# pwr_fpga.net
KiCad netlist of a schematic drawn in Altium Designer
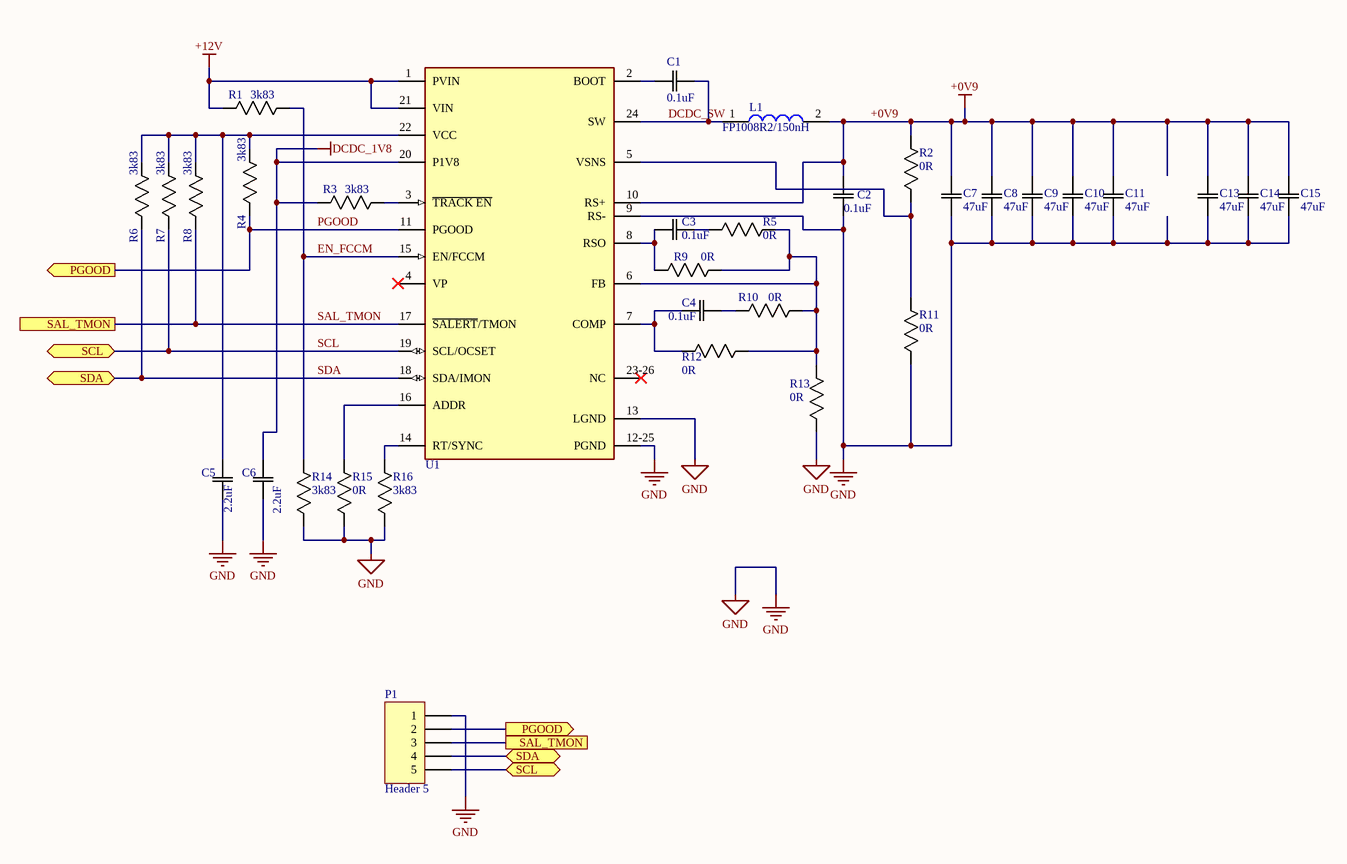
[diagram p0: pwr_fpga.SchDoc]

(export (version "E")
  (design (tool "Eeschema 10.0.6"))
  (components
    (comp (ref "C1")
      (value "0.1uF")
      (footprint "cap_UMK105 CG080CV-F_TAY")
      (description "No Description Available")
      (fields
        (field (name "MANUFACTURER_PART_NUMBER") "TMK105B7103KV-F")
        (field (name "COPYRIGHT") "Copyright (C) 2018 Accelerated Designs. All rights reserved")
      )
      (libsource (lib "2020-09-28_11-29-19") (part "TMK105B7103KV-F"))
    )
    (comp (ref "C2")
      (value "0.1uF")
      (footprint "cap_UMK105 CG080CV-F_TAY")
      (description "No Description Available")
      (fields
        (field (name "MANUFACTURER_PART_NUMBER") "TMK105B7103KV-F")
        (field (name "COPYRIGHT") "Copyright (C) 2018 Accelerated Designs. All rights reserved")
      )
      (libsource (lib "2020-09-28_11-29-19") (part "TMK105B7103KV-F"))
    )
    (comp (ref "C3")
      (value "0.1uF")
      (footprint "cap_UMK105 CG080CV-F_TAY")
      (description "No Description Available")
      (fields
        (field (name "MANUFACTURER_PART_NUMBER") "TMK105B7103KV-F")
        (field (name "COPYRIGHT") "Copyright (C) 2018 Accelerated Designs. All rights reserved")
      )
      (libsource (lib "2020-09-28_11-29-19") (part "TMK105B7103KV-F"))
    )
    (comp (ref "C4")
      (value "0.1uF")
      (footprint "cap_UMK105 CG080CV-F_TAY")
      (description "No Description Available")
      (fields
        (field (name "MANUFACTURER_PART_NUMBER") "TMK105B7103KV-F")
        (field (name "COPYRIGHT") "Copyright (C) 2018 Accelerated Designs. All rights reserved")
      )
      (libsource (lib "2020-09-28_11-29-19") (part "TMK105B7103KV-F"))
    )
    (comp (ref "C5")
      (value "2.2uF")
      (footprint "cap_UMK105 CG080CV-F_TAY")
      (description "No Description Available")
      (fields
        (field (name "MANUFACTURER_PART_NUMBER") "TMK105B7103KV-F")
        (field (name "COPYRIGHT") "Copyright (C) 2018 Accelerated Designs. All rights reserved")
      )
      (libsource (lib "2020-09-28_11-29-19") (part "TMK105B7103KV-F"))
    )
    (comp (ref "C6")
      (value "2.2uF")
      (footprint "cap_UMK105 CG080CV-F_TAY")
      (description "No Description Available")
      (fields
        (field (name "MANUFACTURER_PART_NUMBER") "TMK105B7103KV-F")
        (field (name "COPYRIGHT") "Copyright (C) 2018 Accelerated Designs. All rights reserved")
      )
      (libsource (lib "2020-09-28_11-29-19") (part "TMK105B7103KV-F"))
    )
    (comp (ref "C7")
      (value "47uF")
      (footprint "CAPC220145_140N_KEM")
      (description "No Description Available")
      (fields
        (field (name "MANUFACTURER_PART_NUMBER") "C0805C475K4PAC")
        (field (name "COPYRIGHT") "Copyright (C) 2018 Accelerated Designs. All rights reserved")
      )
      (libsource (lib "2020-10-01_03-11-46") (part "C0805C475K4PAC"))
    )
    (comp (ref "C8")
      (value "47uF")
      (footprint "CAPC220145_140N_KEM")
      (description "No Description Available")
      (fields
        (field (name "MANUFACTURER_PART_NUMBER") "C0805C475K4PAC")
        (field (name "COPYRIGHT") "Copyright (C) 2018 Accelerated Designs. All rights reserved")
      )
      (libsource (lib "2020-10-01_03-11-46") (part "C0805C475K4PAC"))
    )
    (comp (ref "C9")
      (value "47uF")
      (footprint "CAPC220145_140N_KEM")
      (description "No Description Available")
      (fields
        (field (name "MANUFACTURER_PART_NUMBER") "C0805C475K4PAC")
        (field (name "COPYRIGHT") "Copyright (C) 2018 Accelerated Designs. All rights reserved")
      )
      (libsource (lib "2020-10-01_03-11-46") (part "C0805C475K4PAC"))
    )
    (comp (ref "C10")
      (value "47uF")
      (footprint "CAPC220145_140N_KEM")
      (description "No Description Available")
      (fields
        (field (name "MANUFACTURER_PART_NUMBER") "C0805C475K4PAC")
        (field (name "COPYRIGHT") "Copyright (C) 2018 Accelerated Designs. All rights reserved")
      )
      (libsource (lib "2020-10-01_03-11-46") (part "C0805C475K4PAC"))
    )
    (comp (ref "C11")
      (value "47uF")
      (footprint "CAPC220145_140N_KEM")
      (description "No Description Available")
      (fields
        (field (name "MANUFACTURER_PART_NUMBER") "C0805C475K4PAC")
        (field (name "COPYRIGHT") "Copyright (C) 2018 Accelerated Designs. All rights reserved")
      )
      (libsource (lib "2020-10-01_03-11-46") (part "C0805C475K4PAC"))
    )
    (comp (ref "C13")
      (value "47uF")
      (footprint "CAPC220145_140N_KEM")
      (description "No Description Available")
      (fields
        (field (name "MANUFACTURER_PART_NUMBER") "C0805C475K4PAC")
        (field (name "COPYRIGHT") "Copyright (C) 2018 Accelerated Designs. All rights reserved")
      )
      (libsource (lib "2020-10-01_03-11-46") (part "C0805C475K4PAC"))
    )
    (comp (ref "C14")
      (value "47uF")
      (footprint "CAPC220145_140N_KEM")
      (description "No Description Available")
      (fields
        (field (name "MANUFACTURER_PART_NUMBER") "C0805C475K4PAC")
        (field (name "COPYRIGHT") "Copyright (C) 2018 Accelerated Designs. All rights reserved")
      )
      (libsource (lib "2020-10-01_03-11-46") (part "C0805C475K4PAC"))
    )
    (comp (ref "C15")
      (value "47uF")
      (footprint "CAPC220145_140N_KEM")
      (description "No Description Available")
      (fields
        (field (name "MANUFACTURER_PART_NUMBER") "C0805C475K4PAC")
        (field (name "COPYRIGHT") "Copyright (C) 2018 Accelerated Designs. All rights reserved")
      )
      (libsource (lib "2020-10-01_03-11-46") (part "C0805C475K4PAC"))
    )
    (comp (ref "L1")
      (value "FP1008R2/150nH")
      (footprint "SamacSys:INDM10880X800N")
      (description "Inductor")
      (fields
        (field (name "MANUFACTURER_PART_NUMBER") "FP1008R2-R120-R")
        (field (name "MOUSER PART NUMBER") "704-FP1008R2-R120-R")
      )
      (libsource (lib "*") (part "FP1008R2-R120-R"))
    )
    (comp (ref "P1")
      (value "Header 5")
      (footprint "HDR1X5")
      (description "Header, 5-Pin")
      (fields (field (name "PUBLISHER") "Altium Limited"))
      (libsource (lib "Miscellaneous Connectors") (part "Header 5"))
    )
    (comp (ref "R1")
      (value "3k83")
      (footprint "0402_PAN")
      (description "No Description Available")
      (fields
        (field (name "MANUFACTURER_PART_NUMBER") "ERJ2RHD2400X")
        (field (name "COPYRIGHT") "Copyright (C) 2018 Accelerated Designs. All rights reserved")
      )
      (libsource (lib "2020-09-26_12-38-29") (part "ERJ2RHD2400X"))
    )
    (comp (ref "R2")
      (value "0R")
      (footprint "0402_PAN")
      (description "No Description Available")
      (fields
        (field (name "MANUFACTURER_PART_NUMBER") "ERJ2RHD2400X")
        (field (name "COPYRIGHT") "Copyright (C) 2018 Accelerated Designs. All rights reserved")
      )
      (libsource (lib "2020-09-26_12-38-29") (part "ERJ2RHD2400X"))
    )
    (comp (ref "R3")
      (value "3k83")
      (footprint "0402_PAN")
      (description "No Description Available")
      (fields
        (field (name "MANUFACTURER_PART_NUMBER") "ERJ2RHD2400X")
        (field (name "COPYRIGHT") "Copyright (C) 2018 Accelerated Designs. All rights reserved")
      )
      (libsource (lib "2020-09-26_12-38-29") (part "ERJ2RHD2400X"))
    )
    (comp (ref "R4")
      (value "3k83")
      (footprint "0402_PAN")
      (description "No Description Available")
      (fields
        (field (name "MANUFACTURER_PART_NUMBER") "ERJ2RHD2400X")
        (field (name "COPYRIGHT") "Copyright (C) 2018 Accelerated Designs. All rights reserved")
      )
      (libsource (lib "2020-09-26_12-38-29") (part "ERJ2RHD2400X"))
    )
    (comp (ref "R5")
      (value "0R")
      (footprint "0402_PAN")
      (description "No Description Available")
      (fields
        (field (name "MANUFACTURER_PART_NUMBER") "ERJ2RHD2400X")
        (field (name "COPYRIGHT") "Copyright (C) 2018 Accelerated Designs. All rights reserved")
      )
      (libsource (lib "2020-09-26_12-38-29") (part "ERJ2RHD2400X"))
    )
    (comp (ref "R6")
      (value "3k83")
      (footprint "0402_PAN")
      (description "No Description Available")
      (fields
        (field (name "MANUFACTURER_PART_NUMBER") "ERJ2RHD2400X")
        (field (name "COPYRIGHT") "Copyright (C) 2018 Accelerated Designs. All rights reserved")
      )
      (libsource (lib "2020-09-26_12-38-29") (part "ERJ2RHD2400X"))
    )
    (comp (ref "R7")
      (value "3k83")
      (footprint "0402_PAN")
      (description "No Description Available")
      (fields
        (field (name "MANUFACTURER_PART_NUMBER") "ERJ2RHD2400X")
        (field (name "COPYRIGHT") "Copyright (C) 2018 Accelerated Designs. All rights reserved")
      )
      (libsource (lib "2020-09-26_12-38-29") (part "ERJ2RHD2400X"))
    )
    (comp (ref "R8")
      (value "3k83")
      (footprint "0402_PAN")
      (description "No Description Available")
      (fields
        (field (name "MANUFACTURER_PART_NUMBER") "ERJ2RHD2400X")
        (field (name "COPYRIGHT") "Copyright (C) 2018 Accelerated Designs. All rights reserved")
      )
      (libsource (lib "2020-09-26_12-38-29") (part "ERJ2RHD2400X"))
    )
    (comp (ref "R9")
      (value "0R")
      (footprint "0402_PAN")
      (description "No Description Available")
      (fields
        (field (name "MANUFACTURER_PART_NUMBER") "ERJ2RHD2400X")
        (field (name "COPYRIGHT") "Copyright (C) 2018 Accelerated Designs. All rights reserved")
      )
      (libsource (lib "2020-09-26_12-38-29") (part "ERJ2RHD2400X"))
    )
    (comp (ref "R10")
      (value "0R")
      (footprint "0402_PAN")
      (description "No Description Available")
      (fields
        (field (name "MANUFACTURER_PART_NUMBER") "ERJ2RHD2400X")
        (field (name "COPYRIGHT") "Copyright (C) 2018 Accelerated Designs. All rights reserved")
      )
      (libsource (lib "2020-09-26_12-38-29") (part "ERJ2RHD2400X"))
    )
    (comp (ref "R11")
      (value "0R")
      (footprint "0402_PAN")
      (description "No Description Available")
      (fields
        (field (name "MANUFACTURER_PART_NUMBER") "ERJ2RHD2400X")
        (field (name "COPYRIGHT") "Copyright (C) 2018 Accelerated Designs. All rights reserved")
      )
      (libsource (lib "2020-09-26_12-38-29") (part "ERJ2RHD2400X"))
    )
    (comp (ref "R12")
      (value "0R")
      (footprint "0402_PAN")
      (description "No Description Available")
      (fields
        (field (name "MANUFACTURER_PART_NUMBER") "ERJ2RHD2400X")
        (field (name "COPYRIGHT") "Copyright (C) 2018 Accelerated Designs. All rights reserved")
      )
      (libsource (lib "2020-09-26_12-38-29") (part "ERJ2RHD2400X"))
    )
    (comp (ref "R13")
      (value "0R")
      (footprint "0402_PAN")
      (description "No Description Available")
      (fields
        (field (name "MANUFACTURER_PART_NUMBER") "ERJ2RHD2400X")
        (field (name "COPYRIGHT") "Copyright (C) 2018 Accelerated Designs. All rights reserved")
      )
      (libsource (lib "2020-09-26_12-38-29") (part "ERJ2RHD2400X"))
    )
    (comp (ref "R14")
      (value "3k83")
      (footprint "0402_PAN")
      (description "No Description Available")
      (fields
        (field (name "MANUFACTURER_PART_NUMBER") "ERJ2RHD2400X")
        (field (name "COPYRIGHT") "Copyright (C) 2018 Accelerated Designs. All rights reserved")
      )
      (libsource (lib "2020-09-26_12-38-29") (part "ERJ2RHD2400X"))
    )
    (comp (ref "R15")
      (value "0R")
      (footprint "0402_PAN")
      (description "No Description Available")
      (fields
        (field (name "MANUFACTURER_PART_NUMBER") "ERJ2RHD2400X")
        (field (name "COPYRIGHT") "Copyright (C) 2018 Accelerated Designs. All rights reserved")
      )
      (libsource (lib "2020-09-26_12-38-29") (part "ERJ2RHD2400X"))
    )
    (comp (ref "R16")
      (value "3k83")
      (footprint "0402_PAN")
      (description "No Description Available")
      (fields
        (field (name "MANUFACTURER_PART_NUMBER") "ERJ2RHD2400X")
        (field (name "COPYRIGHT") "Copyright (C) 2018 Accelerated Designs. All rights reserved")
      )
      (libsource (lib "2020-09-26_12-38-29") (part "ERJ2RHD2400X"))
    )
    (comp (ref "U1")
      (value "IR38064MTRPBF")
      (footprint "Infineon_Technologies_PG-IQFN-34_MFG")
      (libsource (lib "IR38064MTRPBF") (part "IR38064MTRPBF"))
    )
  )
  (nets
    (net (code "1") (name "+0V9") (class "Default")
      (node (ref "C10") (pin "2") (pinfunction "2_2") (pintype "passive"))
      (node (ref "C11") (pin "2") (pinfunction "2_2") (pintype "passive"))
      (node (ref "C13") (pin "2") (pinfunction "2_2") (pintype "passive"))
      (node (ref "C14") (pin "2") (pinfunction "2_2") (pintype "passive"))
      (node (ref "C15") (pin "2") (pinfunction "2_2") (pintype "passive"))
      (node (ref "C2") (pin "2") (pinfunction "2_2") (pintype "passive"))
      (node (ref "C7") (pin "2") (pinfunction "2_2") (pintype "passive"))
      (node (ref "C8") (pin "2") (pinfunction "2_2") (pintype "passive"))
      (node (ref "C9") (pin "2") (pinfunction "2_2") (pintype "passive"))
      (node (ref "L1") (pin "2") (pinfunction "2_2") (pintype "passive"))
      (node (ref "R2") (pin "1") (pinfunction "1_1") (pintype "passive"))
      (node (ref "U1") (pin "10") (pinfunction "RS+_10") (pintype "tri_state"))
    )
    (net (code "2") (name "+12V") (class "Default")
      (node (ref "R1") (pin "2") (pinfunction "2_2") (pintype "passive"))
      (node (ref "U1") (pin "1") (pinfunction "PVIN_1") (pintype "power_in"))
      (node (ref "U1") (pin "21") (pinfunction "VIN_21") (pintype "power_in"))
    )
    (net (code "3") (name "/DCDC_SW") (class "Default")
      (node (ref "C1") (pin "2") (pinfunction "2_2") (pintype "passive"))
      (node (ref "L1") (pin "1") (pinfunction "1_1") (pintype "passive"))
      (node (ref "U1") (pin "24") (pinfunction "SW_24") (pintype "passive"))
    )
    (net (code "4") (name "/EN_FCCM") (class "Default")
      (node (ref "R1") (pin "1") (pinfunction "1_1") (pintype "passive"))
      (node (ref "R14") (pin "1") (pinfunction "1_1") (pintype "passive"))
      (node (ref "U1") (pin "15") (pinfunction "EN/FCCM_15") (pintype "input"))
    )
    (net (code "5") (name "/PGOOD") (class "Default")
      (node (ref "P1") (pin "2") (pinfunction "2_2") (pintype "passive"))
      (node (ref "R4") (pin "1") (pinfunction "1_1") (pintype "passive"))
      (node (ref "U1") (pin "11") (pinfunction "PGOOD_11") (pintype "open_collector"))
    )
    (net (code "6") (name "/SAL_TMON") (class "Default")
      (node (ref "P1") (pin "3") (pinfunction "3_3") (pintype "passive"))
      (node (ref "R8") (pin "1") (pinfunction "1_1") (pintype "passive"))
      (node (ref "U1") (pin "17") (pinfunction "~{SALERT}/TMON_17") (pintype "open_collector"))
    )
    (net (code "7") (name "/SCL") (class "Default")
      (node (ref "P1") (pin "5") (pinfunction "5_5") (pintype "passive"))
      (node (ref "R7") (pin "1") (pinfunction "1_1") (pintype "passive"))
      (node (ref "U1") (pin "19") (pinfunction "SCL/OCSET_19") (pintype "bidirectional"))
    )
    (net (code "8") (name "/SDA") (class "Default")
      (node (ref "P1") (pin "4") (pinfunction "4_4") (pintype "passive"))
      (node (ref "R6") (pin "1") (pinfunction "1_1") (pintype "passive"))
      (node (ref "U1") (pin "18") (pinfunction "SDA/IMON_18") (pintype "bidirectional"))
    )
    (net (code "9") (name "DCDC_1V8") (class "Default")
      (node (ref "C6") (pin "2") (pinfunction "2_2") (pintype "passive"))
      (node (ref "R3") (pin "2") (pinfunction "2_2") (pintype "passive"))
      (node (ref "U1") (pin "20") (pinfunction "P1V8_20") (pintype "power_in"))
    )
    (net (code "10") (name "GND") (class "Default")
      (node (ref "C10") (pin "1") (pinfunction "1_1") (pintype "passive"))
      (node (ref "C11") (pin "1") (pinfunction "1_1") (pintype "passive"))
      (node (ref "C13") (pin "1") (pinfunction "1_1") (pintype "passive"))
      (node (ref "C14") (pin "1") (pinfunction "1_1") (pintype "passive"))
      (node (ref "C15") (pin "1") (pinfunction "1_1") (pintype "passive"))
      (node (ref "C2") (pin "1") (pinfunction "1_1") (pintype "passive"))
      (node (ref "C5") (pin "1") (pinfunction "1_1") (pintype "passive"))
      (node (ref "C6") (pin "1") (pinfunction "1_1") (pintype "passive"))
      (node (ref "C7") (pin "1") (pinfunction "1_1") (pintype "passive"))
      (node (ref "C8") (pin "1") (pinfunction "1_1") (pintype "passive"))
      (node (ref "C9") (pin "1") (pinfunction "1_1") (pintype "passive"))
      (node (ref "P1") (pin "1") (pinfunction "1_1") (pintype "passive"))
      (node (ref "R11") (pin "2") (pinfunction "2_2") (pintype "passive"))
      (node (ref "R13") (pin "2") (pinfunction "2_2") (pintype "passive"))
      (node (ref "R14") (pin "2") (pinfunction "2_2") (pintype "passive"))
      (node (ref "R15") (pin "1") (pinfunction "1_1") (pintype "passive"))
      (node (ref "R16") (pin "1") (pinfunction "1_1") (pintype "passive"))
      (node (ref "U1") (pin "12-25") (pinfunction "PGND_12-25") (pintype "power_in"))
      (node (ref "U1") (pin "13") (pinfunction "LGND_13") (pintype "power_in"))
      (node (ref "U1") (pin "9") (pinfunction "RS-_9") (pintype "tri_state"))
    )
    (net (code "11") (name "Net-(C3-Pad2)") (class "Default")
      (node (ref "C3") (pin "2") (pinfunction "2_2") (pintype "passive"))
      (node (ref "R5") (pin "2") (pinfunction "2_2") (pintype "passive"))
    )
    (net (code "12") (name "Net-(C4-Pad2)") (class "Default")
      (node (ref "C4") (pin "2") (pinfunction "2_2") (pintype "passive"))
      (node (ref "R10") (pin "2") (pinfunction "2_2") (pintype "passive"))
    )
    (net (code "13") (name "Net-(U1-ADDR)") (class "Default")
      (node (ref "R15") (pin "2") (pinfunction "2_2") (pintype "passive"))
      (node (ref "U1") (pin "16") (pinfunction "ADDR_16") (pintype "passive"))
    )
    (net (code "14") (name "Net-(U1-BOOT)") (class "Default")
      (node (ref "C1") (pin "1") (pinfunction "1_1") (pintype "passive"))
      (node (ref "U1") (pin "2") (pinfunction "BOOT_2") (pintype "passive"))
    )
    (net (code "15") (name "Net-(U1-COMP)") (class "Default")
      (node (ref "C4") (pin "1") (pinfunction "1_1") (pintype "passive"))
      (node (ref "R12") (pin "2") (pinfunction "2_2") (pintype "passive"))
      (node (ref "U1") (pin "7") (pinfunction "COMP_7") (pintype "passive"))
    )
    (net (code "16") (name "Net-(U1-FB)") (class "Default")
      (node (ref "R10") (pin "1") (pinfunction "1_1") (pintype "passive"))
      (node (ref "R12") (pin "1") (pinfunction "1_1") (pintype "passive"))
      (node (ref "R13") (pin "1") (pinfunction "1_1") (pintype "passive"))
      (node (ref "R5") (pin "1") (pinfunction "1_1") (pintype "passive"))
      (node (ref "R9") (pin "1") (pinfunction "1_1") (pintype "passive"))
      (node (ref "U1") (pin "6") (pinfunction "FB_6") (pintype "passive"))
    )
    (net (code "17") (name "Net-(U1-RSO)") (class "Default")
      (node (ref "C3") (pin "1") (pinfunction "1_1") (pintype "passive"))
      (node (ref "R9") (pin "2") (pinfunction "2_2") (pintype "passive"))
      (node (ref "U1") (pin "8") (pinfunction "RSO_8") (pintype "passive"))
    )
    (net (code "18") (name "Net-(U1-RT{slash}SYNC)") (class "Default")
      (node (ref "R16") (pin "2") (pinfunction "2_2") (pintype "passive"))
      (node (ref "U1") (pin "14") (pinfunction "RT/SYNC_14") (pintype "passive"))
    )
    (net (code "19") (name "Net-(U1-VCC)") (class "Default")
      (node (ref "C5") (pin "2") (pinfunction "2_2") (pintype "passive"))
      (node (ref "R4") (pin "2") (pinfunction "2_2") (pintype "passive"))
      (node (ref "R6") (pin "2") (pinfunction "2_2") (pintype "passive"))
      (node (ref "R7") (pin "2") (pinfunction "2_2") (pintype "passive"))
      (node (ref "R8") (pin "2") (pinfunction "2_2") (pintype "passive"))
      (node (ref "U1") (pin "22") (pinfunction "VCC_22") (pintype "passive"))
    )
    (net (code "20") (name "Net-(U1-VSNS)") (class "Default")
      (node (ref "R11") (pin "1") (pinfunction "1_1") (pintype "passive"))
      (node (ref "R2") (pin "2") (pinfunction "2_2") (pintype "passive"))
      (node (ref "U1") (pin "5") (pinfunction "VSNS_5") (pintype "passive"))
    )
    (net (code "21") (name "Net-(U1-~{TRACK_EN})") (class "Default")
      (node (ref "R3") (pin "1") (pinfunction "1_1") (pintype "passive"))
      (node (ref "U1") (pin "3") (pinfunction "~{TRACK_EN}_3") (pintype "input"))
    )
    (net (code "22") (name "unconnected-(U1-NC-Pad23-26)") (class "Default")
      (node (ref "U1") (pin "23-26") (pinfunction "NC_23-26") (pintype "passive+no_connect"))
    )
    (net (code "23") (name "unconnected-(U1-VP-Pad4)") (class "Default")
      (node (ref "U1") (pin "4") (pinfunction "VP_4") (pintype "passive+no_connect"))
    )
  )
)
